# processor_breakout_conn.net
KiCad netlist of a schematic drawn in Altium Designer
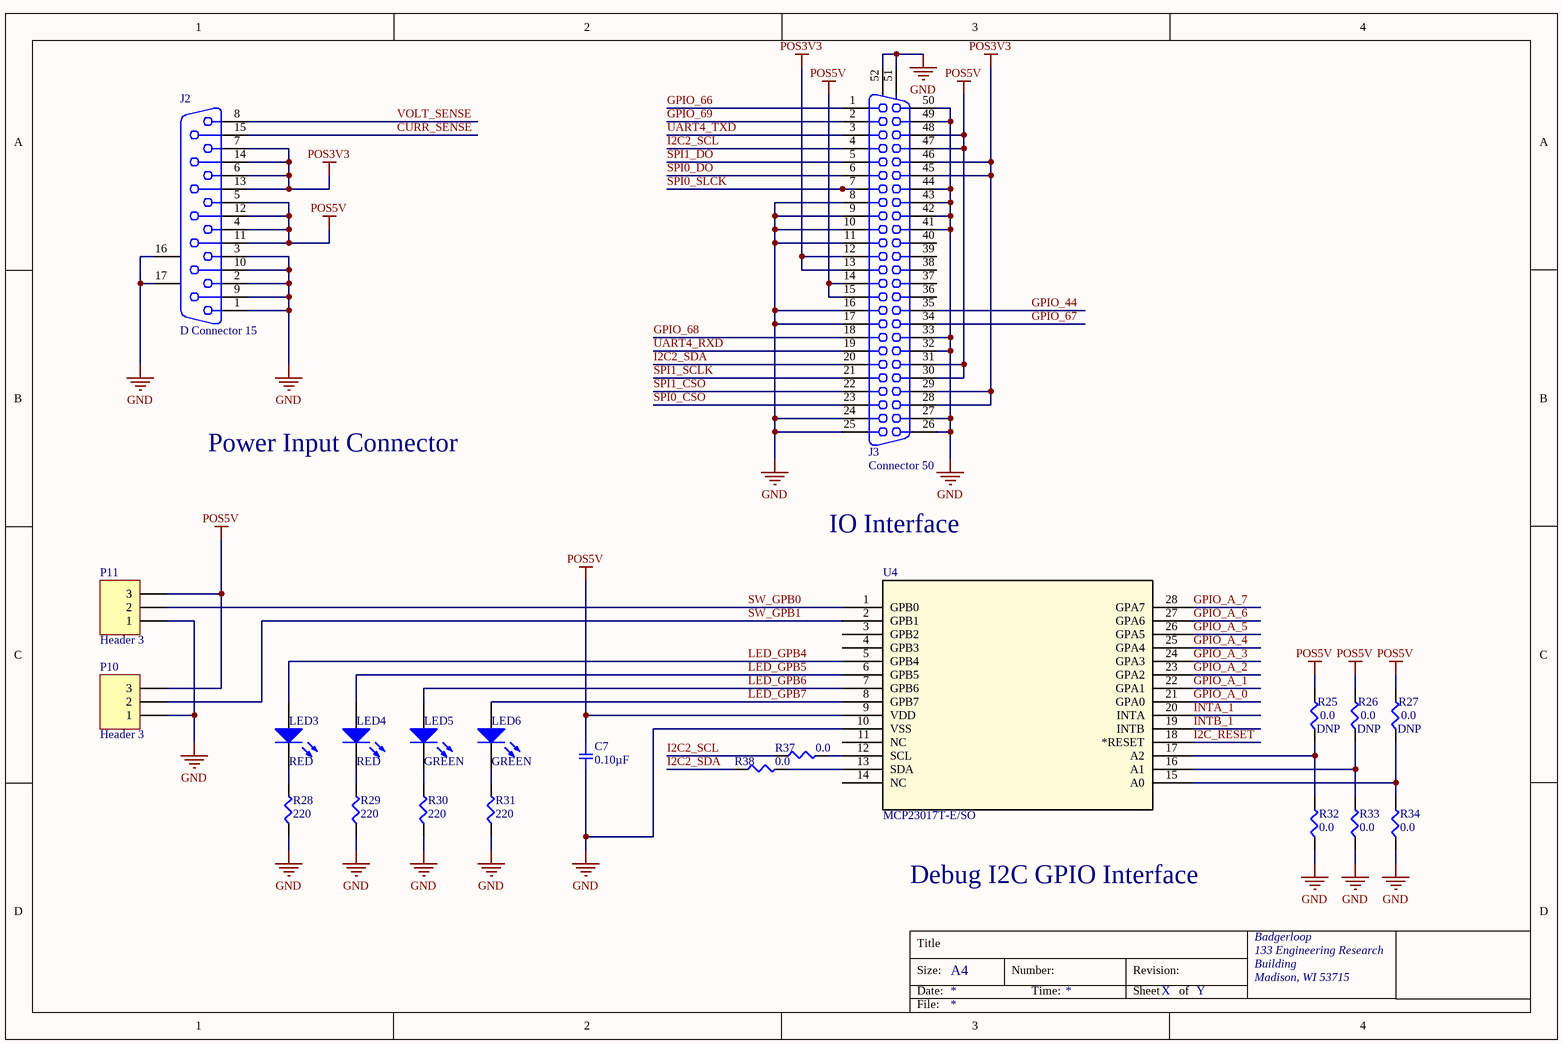
[diagram p0: processor_breakout_conn.SchDoc]

(export (version "E")
  (design (tool "Eeschema 10.0.6"))
  (components
    (comp (ref "C7")
      (value "0.10µF")
      (footprint "SMD-0603C")
      (description "CAP CER 0.1UF 100V X7R 0603")
      (fields
        (field (name "DIGI-KEY PART NUMBER") "490-13420-1-ND")
        (field (name "PART NUMBER") "GCJ188R72A104KA01D")
      )
      (libsource (lib "capacitor") (part "GCJ188R72A104KA01D"))
    )
    (comp (ref "J2")
      (value "D Connector 15")
      (footprint "DSUB1.385-2H15")
      (description "Receptacle Assembly, 15 Position, Right Angle")
      (fields (field (name "PUBLISHER") "Altium Limited"))
      (libsource (lib "connector") (part "D Connector 15"))
    )
    (comp (ref "J3")
      (value "Connector 50")
      (footprint "050DSUB1.27-H96")
      (description "Receptacle Header Assemby")
      (fields (field (name "PUBLISHER") "Altium Limited"))
      (libsource (lib "temp") (part "Connector 50"))
    )
    (comp (ref "LED3")
      (value "RED")
      (footprint "LED 0603 RED")
      (description "Red 631nm LED Indication - Discrete 2V 0603 (1608 Metric)")
      (fields (field (name "MANUFACTURER") "Lite-On Inc."))
      (libsource (lib "misc") (part "LED RED 0603"))
    )
    (comp (ref "LED4")
      (value "RED")
      (footprint "LED 0603 RED")
      (description "Red 631nm LED Indication - Discrete 2V 0603 (1608 Metric)")
      (fields (field (name "MANUFACTURER") "Lite-On Inc."))
      (libsource (lib "misc") (part "LED RED 0603"))
    )
    (comp (ref "LED5")
      (value "GREEN")
      (footprint "LED 0603 GREEN")
      (fields (field (name "MANUFACTURER") "Lite-On Inc."))
      (libsource (lib "misc") (part "LED GREEN 0603"))
    )
    (comp (ref "LED6")
      (value "GREEN")
      (footprint "LED 0603 GREEN")
      (fields (field (name "MANUFACTURER") "Lite-On Inc."))
      (libsource (lib "misc") (part "LED GREEN 0603"))
    )
    (comp (ref "P10")
      (value "Header 3")
      (footprint "Pin Header 1x3 TH Pitch 2.54mm")
      (description "Header, 3-Pin")
      (fields (field (name "PUBLISHER") "Altium Limited"))
      (libsource (lib "connector") (part "Header 3"))
    )
    (comp (ref "P11")
      (value "Header 3")
      (footprint "Pin Header 1x3 TH Pitch 2.54mm")
      (description "Header, 3-Pin")
      (fields (field (name "PUBLISHER") "Altium Limited"))
      (libsource (lib "connector") (part "Header 3"))
    )
    (comp (ref "R25")
      (value "0.0")
      (footprint "SMD-0402-RES")
      (description "RES SMD 0.0OHM JUMPER 1/10W 0402")
      (fields
        (field (name "PART NUMBER") "ERJ-2GE0R00X")
        (field (name "DIGI-KEY PART NUMBER") "P0.0JCT-ND")
        (field (name "DNP") "DNP")
      )
      (libsource (lib "resistor") (part "ERJ-2GE0R00X"))
    )
    (comp (ref "R26")
      (value "0.0")
      (footprint "SMD-0402-RES")
      (description "RES SMD 0.0OHM JUMPER 1/10W 0402")
      (fields
        (field (name "PART NUMBER") "ERJ-2GE0R00X")
        (field (name "DIGI-KEY PART NUMBER") "P0.0JCT-ND")
        (field (name "DNP") "DNP")
      )
      (libsource (lib "resistor") (part "ERJ-2GE0R00X"))
    )
    (comp (ref "R27")
      (value "0.0")
      (footprint "SMD-0402-RES")
      (description "RES SMD 0.0OHM JUMPER 1/10W 0402")
      (fields
        (field (name "PART NUMBER") "ERJ-2GE0R00X")
        (field (name "DIGI-KEY PART NUMBER") "P0.0JCT-ND")
        (field (name "DNP") "DNP")
      )
      (libsource (lib "resistor") (part "ERJ-2GE0R00X"))
    )
    (comp (ref "R28")
      (value "220")
      (footprint "SMD-0805-RES")
      (description "RES SMD 220 OHM 1% 1/8W 0805")
      (fields (field (name "PART NUMBER") "ERJ-6ENF2200V") (field (name "DIGI-KEY PART NUMBER") "P220CCT-ND"))
      (libsource (lib "resistor") (part "ERJ-6ENF2200V"))
    )
    (comp (ref "R29")
      (value "220")
      (footprint "SMD-0805-RES")
      (description "RES SMD 220 OHM 1% 1/8W 0805")
      (fields (field (name "PART NUMBER") "ERJ-6ENF2200V") (field (name "DIGI-KEY PART NUMBER") "P220CCT-ND"))
      (libsource (lib "resistor") (part "ERJ-6ENF2200V"))
    )
    (comp (ref "R30")
      (value "220")
      (footprint "SMD-0805-RES")
      (description "RES SMD 220 OHM 1% 1/8W 0805")
      (fields (field (name "PART NUMBER") "ERJ-6ENF2200V") (field (name "DIGI-KEY PART NUMBER") "P220CCT-ND"))
      (libsource (lib "resistor") (part "ERJ-6ENF2200V"))
    )
    (comp (ref "R31")
      (value "220")
      (footprint "SMD-0805-RES")
      (description "RES SMD 220 OHM 1% 1/8W 0805")
      (fields (field (name "PART NUMBER") "ERJ-6ENF2200V") (field (name "DIGI-KEY PART NUMBER") "P220CCT-ND"))
      (libsource (lib "resistor") (part "ERJ-6ENF2200V"))
    )
    (comp (ref "R32")
      (value "0.0")
      (footprint "SMD-0402-RES")
      (description "RES SMD 0.0OHM JUMPER 1/10W 0402")
      (fields (field (name "PART NUMBER") "ERJ-2GE0R00X") (field (name "DIGI-KEY PART NUMBER") "P0.0JCT-ND"))
      (libsource (lib "resistor") (part "ERJ-2GE0R00X"))
    )
    (comp (ref "R33")
      (value "0.0")
      (footprint "SMD-0402-RES")
      (description "RES SMD 0.0OHM JUMPER 1/10W 0402")
      (fields (field (name "PART NUMBER") "ERJ-2GE0R00X") (field (name "DIGI-KEY PART NUMBER") "P0.0JCT-ND"))
      (libsource (lib "resistor") (part "ERJ-2GE0R00X"))
    )
    (comp (ref "R34")
      (value "0.0")
      (footprint "SMD-0402-RES")
      (description "RES SMD 0.0OHM JUMPER 1/10W 0402")
      (fields (field (name "PART NUMBER") "ERJ-2GE0R00X") (field (name "DIGI-KEY PART NUMBER") "P0.0JCT-ND"))
      (libsource (lib "resistor") (part "ERJ-2GE0R00X"))
    )
    (comp (ref "R37")
      (value "0.0")
      (footprint "SMD-0402-RES")
      (description "RES SMD 0.0OHM JUMPER 1/10W 0402")
      (fields (field (name "PART NUMBER") "ERJ-2GE0R00X") (field (name "DIGI-KEY PART NUMBER") "P0.0JCT-ND"))
      (libsource (lib "resistor") (part "ERJ-2GE0R00X"))
    )
    (comp (ref "R38")
      (value "0.0")
      (footprint "SMD-0402-RES")
      (description "RES SMD 0.0OHM JUMPER 1/10W 0402")
      (fields (field (name "PART NUMBER") "ERJ-2GE0R00X") (field (name "DIGI-KEY PART NUMBER") "P0.0JCT-ND"))
      (libsource (lib "resistor") (part "ERJ-2GE0R00X"))
    )
    (comp (ref "U4")
      (value "MCP23017T-E/SO")
      (footprint "SOIC28-W_MC-M")
      (description "Imported")
      (libsource (lib "temp") (part "MCP23017T-E/SO"))
    )
  )
  (nets
    (net (code "1") (name "/CURR_SENSE") (class "Default")
      (node (ref "J2") (pin "15") (pinfunction "15_15") (pintype "passive"))
    )
    (net (code "2") (name "/GPIO_44") (class "Default")
      (node (ref "J3") (pin "35") (pinfunction "35_35") (pintype "passive"))
    )
    (net (code "3") (name "/GPIO_66") (class "Default")
      (node (ref "J3") (pin "1") (pinfunction "1_1") (pintype "passive"))
    )
    (net (code "4") (name "/GPIO_67") (class "Default")
      (node (ref "J3") (pin "34") (pinfunction "34_34") (pintype "passive"))
    )
    (net (code "5") (name "/GPIO_68") (class "Default")
      (node (ref "J3") (pin "18") (pinfunction "18_18") (pintype "passive"))
    )
    (net (code "6") (name "/GPIO_69") (class "Default")
      (node (ref "J3") (pin "2") (pinfunction "2_2") (pintype "passive"))
    )
    (net (code "7") (name "/GPIO_A_0") (class "Default")
      (node (ref "U4") (pin "21") (pinfunction "GPA0_21") (pintype "passive"))
    )
    (net (code "8") (name "/GPIO_A_1") (class "Default")
      (node (ref "U4") (pin "22") (pinfunction "GPA1_22") (pintype "passive"))
    )
    (net (code "9") (name "/GPIO_A_2") (class "Default")
      (node (ref "U4") (pin "23") (pinfunction "GPA2_23") (pintype "passive"))
    )
    (net (code "10") (name "/GPIO_A_3") (class "Default")
      (node (ref "U4") (pin "24") (pinfunction "GPA3_24") (pintype "passive"))
    )
    (net (code "11") (name "/GPIO_A_4") (class "Default")
      (node (ref "U4") (pin "25") (pinfunction "GPA4_25") (pintype "passive"))
    )
    (net (code "12") (name "/GPIO_A_5") (class "Default")
      (node (ref "U4") (pin "26") (pinfunction "GPA5_26") (pintype "passive"))
    )
    (net (code "13") (name "/GPIO_A_6") (class "Default")
      (node (ref "U4") (pin "27") (pinfunction "GPA6_27") (pintype "passive"))
    )
    (net (code "14") (name "/GPIO_A_7") (class "Default")
      (node (ref "U4") (pin "28") (pinfunction "GPA7_28") (pintype "passive"))
    )
    (net (code "15") (name "/I2C2_SCL") (class "Default")
      (node (ref "J3") (pin "4") (pinfunction "4_4") (pintype "passive"))
      (node (ref "R37") (pin "1") (pinfunction "1_1") (pintype "passive"))
    )
    (net (code "16") (name "/I2C2_SDA") (class "Default")
      (node (ref "J3") (pin "20") (pinfunction "20_20") (pintype "passive"))
      (node (ref "R38") (pin "1") (pinfunction "1_1") (pintype "passive"))
    )
    (net (code "17") (name "/I2C_RESET") (class "Default")
      (node (ref "U4") (pin "18") (pinfunction "*RESET_18") (pintype "passive"))
    )
    (net (code "18") (name "/INTA_1") (class "Default")
      (node (ref "U4") (pin "20") (pinfunction "INTA_20") (pintype "passive"))
    )
    (net (code "19") (name "/INTB_1") (class "Default")
      (node (ref "U4") (pin "19") (pinfunction "INTB_19") (pintype "passive"))
    )
    (net (code "20") (name "/LED_GPB4") (class "Default")
      (node (ref "LED3") (pin "1") (pinfunction "A_1") (pintype "passive"))
      (node (ref "U4") (pin "5") (pinfunction "GPB4_5") (pintype "passive"))
    )
    (net (code "21") (name "/LED_GPB5") (class "Default")
      (node (ref "LED4") (pin "1") (pinfunction "A_1") (pintype "passive"))
      (node (ref "U4") (pin "6") (pinfunction "GPB5_6") (pintype "passive"))
    )
    (net (code "22") (name "/LED_GPB6") (class "Default")
      (node (ref "LED5") (pin "1") (pinfunction "A_1") (pintype "passive"))
      (node (ref "U4") (pin "7") (pinfunction "GPB6_7") (pintype "passive"))
    )
    (net (code "23") (name "/LED_GPB7") (class "Default")
      (node (ref "LED6") (pin "1") (pinfunction "A_1") (pintype "passive"))
      (node (ref "U4") (pin "8") (pinfunction "GPB7_8") (pintype "passive"))
    )
    (net (code "24") (name "/SPI0_CSO") (class "Default")
      (node (ref "J3") (pin "23") (pinfunction "23_23") (pintype "passive"))
    )
    (net (code "25") (name "/SPI0_DO") (class "Default")
      (node (ref "J3") (pin "6") (pinfunction "6_6") (pintype "passive"))
    )
    (net (code "26") (name "/SPI0_SLCK") (class "Default")
      (node (ref "J3") (pin "7") (pinfunction "7_7") (pintype "passive"))
    )
    (net (code "27") (name "/SPI1_CSO") (class "Default")
      (node (ref "J3") (pin "22") (pinfunction "22_22") (pintype "passive"))
    )
    (net (code "28") (name "/SPI1_DO") (class "Default")
      (node (ref "J3") (pin "5") (pinfunction "5_5") (pintype "passive"))
    )
    (net (code "29") (name "/SPI1_SCLK") (class "Default")
      (node (ref "J3") (pin "21") (pinfunction "21_21") (pintype "passive"))
    )
    (net (code "30") (name "/SW_GPB0") (class "Default")
      (node (ref "P11") (pin "2") (pinfunction "2_2") (pintype "passive"))
      (node (ref "U4") (pin "1") (pinfunction "GPB0_1") (pintype "passive"))
    )
    (net (code "31") (name "/SW_GPB1") (class "Default")
      (node (ref "P10") (pin "2") (pinfunction "2_2") (pintype "passive"))
      (node (ref "U4") (pin "2") (pinfunction "GPB1_2") (pintype "passive"))
    )
    (net (code "32") (name "/UART4_RXD") (class "Default")
      (node (ref "J3") (pin "19") (pinfunction "19_19") (pintype "passive"))
    )
    (net (code "33") (name "/UART4_TXD") (class "Default")
      (node (ref "J3") (pin "3") (pinfunction "3_3") (pintype "passive"))
    )
    (net (code "34") (name "/VOLT_SENSE") (class "Default")
      (node (ref "J2") (pin "8") (pinfunction "8_8") (pintype "passive"))
    )
    (net (code "35") (name "GND") (class "Default")
      (node (ref "C7") (pin "2") (pinfunction "2_2") (pintype "passive"))
      (node (ref "J2") (pin "1") (pinfunction "1_1") (pintype "passive"))
      (node (ref "J2") (pin "10") (pinfunction "10_10") (pintype "passive"))
      (node (ref "J2") (pin "16") (pinfunction "MH1_16") (pintype "passive"))
      (node (ref "J2") (pin "17") (pinfunction "MH2_17") (pintype "passive"))
      (node (ref "J2") (pin "2") (pinfunction "2_2") (pintype "passive"))
      (node (ref "J2") (pin "3") (pinfunction "3_3") (pintype "passive"))
      (node (ref "J2") (pin "9") (pinfunction "9_9") (pintype "passive"))
      (node (ref "J3") (pin "10") (pinfunction "10_10") (pintype "passive"))
      (node (ref "J3") (pin "11") (pinfunction "11_11") (pintype "passive"))
      (node (ref "J3") (pin "16") (pinfunction "16_16") (pintype "passive"))
      (node (ref "J3") (pin "17") (pinfunction "17_17") (pintype "passive"))
      (node (ref "J3") (pin "24") (pinfunction "24_24") (pintype "passive"))
      (node (ref "J3") (pin "25") (pinfunction "25_25") (pintype "passive"))
      (node (ref "J3") (pin "26") (pinfunction "26_26") (pintype "passive"))
      (node (ref "J3") (pin "27") (pinfunction "27_27") (pintype "passive"))
      (node (ref "J3") (pin "32") (pinfunction "32_32") (pintype "passive"))
      (node (ref "J3") (pin "33") (pinfunction "33_33") (pintype "passive"))
      (node (ref "J3") (pin "41") (pinfunction "41_41") (pintype "passive"))
      (node (ref "J3") (pin "42") (pinfunction "42_42") (pintype "passive"))
      (node (ref "J3") (pin "43") (pinfunction "43_43") (pintype "passive"))
      (node (ref "J3") (pin "44") (pinfunction "44_44") (pintype "passive"))
      (node (ref "J3") (pin "49") (pinfunction "49_49") (pintype "passive"))
      (node (ref "J3") (pin "50") (pinfunction "50_50") (pintype "passive"))
      (node (ref "J3") (pin "51") (pinfunction "51_51") (pintype "passive"))
      (node (ref "J3") (pin "52") (pinfunction "52_52") (pintype "passive"))
      (node (ref "J3") (pin "8") (pinfunction "8_8") (pintype "passive"))
      (node (ref "J3") (pin "9") (pinfunction "9_9") (pintype "passive"))
      (node (ref "P10") (pin "1") (pinfunction "1_1") (pintype "passive"))
      (node (ref "P11") (pin "1") (pinfunction "1_1") (pintype "passive"))
      (node (ref "R28") (pin "1") (pinfunction "1_1") (pintype "passive"))
      (node (ref "R29") (pin "1") (pinfunction "1_1") (pintype "passive"))
      (node (ref "R30") (pin "1") (pinfunction "1_1") (pintype "passive"))
      (node (ref "R31") (pin "1") (pinfunction "1_1") (pintype "passive"))
      (node (ref "R32") (pin "1") (pinfunction "1_1") (pintype "passive"))
      (node (ref "R33") (pin "1") (pinfunction "1_1") (pintype "passive"))
      (node (ref "R34") (pin "1") (pinfunction "1_1") (pintype "passive"))
      (node (ref "U4") (pin "10") (pinfunction "VSS_10") (pintype "passive"))
    )
    (net (code "36") (name "Net-(LED3-K)") (class "Default")
      (node (ref "LED3") (pin "2") (pinfunction "K_2") (pintype "passive"))
      (node (ref "R28") (pin "2") (pinfunction "2_2") (pintype "passive"))
    )
    (net (code "37") (name "Net-(LED4-K)") (class "Default")
      (node (ref "LED4") (pin "2") (pinfunction "K_2") (pintype "passive"))
      (node (ref "R29") (pin "2") (pinfunction "2_2") (pintype "passive"))
    )
    (net (code "38") (name "Net-(LED5-K)") (class "Default")
      (node (ref "LED5") (pin "2") (pinfunction "K_2") (pintype "passive"))
      (node (ref "R30") (pin "2") (pinfunction "2_2") (pintype "passive"))
    )
    (net (code "39") (name "Net-(LED6-K)") (class "Default")
      (node (ref "LED6") (pin "2") (pinfunction "K_2") (pintype "passive"))
      (node (ref "R31") (pin "2") (pinfunction "2_2") (pintype "passive"))
    )
    (net (code "40") (name "Net-(U4-A0)") (class "Default")
      (node (ref "R27") (pin "1") (pinfunction "1_1") (pintype "passive"))
      (node (ref "R34") (pin "2") (pinfunction "2_2") (pintype "passive"))
      (node (ref "U4") (pin "15") (pinfunction "A0_15") (pintype "passive"))
    )
    (net (code "41") (name "Net-(U4-A1)") (class "Default")
      (node (ref "R26") (pin "1") (pinfunction "1_1") (pintype "passive"))
      (node (ref "R33") (pin "2") (pinfunction "2_2") (pintype "passive"))
      (node (ref "U4") (pin "16") (pinfunction "A1_16") (pintype "passive"))
    )
    (net (code "42") (name "Net-(U4-A2)") (class "Default")
      (node (ref "R25") (pin "1") (pinfunction "1_1") (pintype "passive"))
      (node (ref "R32") (pin "2") (pinfunction "2_2") (pintype "passive"))
      (node (ref "U4") (pin "17") (pinfunction "A2_17") (pintype "passive"))
    )
    (net (code "43") (name "Net-(U4-SCL)") (class "Default")
      (node (ref "R37") (pin "2") (pinfunction "2_2") (pintype "passive"))
      (node (ref "U4") (pin "12") (pinfunction "SCL_12") (pintype "passive"))
    )
    (net (code "44") (name "Net-(U4-SDA)") (class "Default")
      (node (ref "R38") (pin "2") (pinfunction "2_2") (pintype "passive"))
      (node (ref "U4") (pin "13") (pinfunction "SDA_13") (pintype "passive"))
    )
    (net (code "45") (name "POS3V3") (class "Default")
      (node (ref "J2") (pin "13") (pinfunction "13_13") (pintype "passive"))
      (node (ref "J2") (pin "14") (pinfunction "14_14") (pintype "passive"))
      (node (ref "J2") (pin "6") (pinfunction "6_6") (pintype "passive"))
      (node (ref "J2") (pin "7") (pinfunction "7_7") (pintype "passive"))
      (node (ref "J3") (pin "12") (pinfunction "12_12") (pintype "passive"))
      (node (ref "J3") (pin "13") (pinfunction "13_13") (pintype "passive"))
      (node (ref "J3") (pin "28") (pinfunction "28_28") (pintype "passive"))
      (node (ref "J3") (pin "29") (pinfunction "29_29") (pintype "passive"))
      (node (ref "J3") (pin "45") (pinfunction "45_45") (pintype "passive"))
      (node (ref "J3") (pin "46") (pinfunction "46_46") (pintype "passive"))
    )
    (net (code "46") (name "POS5V") (class "Default")
      (node (ref "C7") (pin "1") (pinfunction "1_1") (pintype "passive"))
      (node (ref "J2") (pin "11") (pinfunction "11_11") (pintype "passive"))
      (node (ref "J2") (pin "12") (pinfunction "12_12") (pintype "passive"))
      (node (ref "J2") (pin "4") (pinfunction "4_4") (pintype "passive"))
      (node (ref "J2") (pin "5") (pinfunction "5_5") (pintype "passive"))
      (node (ref "J3") (pin "14") (pinfunction "14_14") (pintype "passive"))
      (node (ref "J3") (pin "15") (pinfunction "15_15") (pintype "passive"))
      (node (ref "J3") (pin "30") (pinfunction "30_30") (pintype "passive"))
      (node (ref "J3") (pin "31") (pinfunction "31_31") (pintype "passive"))
      (node (ref "J3") (pin "47") (pinfunction "47_47") (pintype "passive"))
      (node (ref "J3") (pin "48") (pinfunction "48_48") (pintype "passive"))
      (node (ref "P10") (pin "3") (pinfunction "3_3") (pintype "passive"))
      (node (ref "P11") (pin "3") (pinfunction "3_3") (pintype "passive"))
      (node (ref "R25") (pin "2") (pinfunction "2_2") (pintype "passive"))
      (node (ref "R26") (pin "2") (pinfunction "2_2") (pintype "passive"))
      (node (ref "R27") (pin "2") (pinfunction "2_2") (pintype "passive"))
      (node (ref "U4") (pin "9") (pinfunction "VDD_9") (pintype "passive"))
    )
    (net (code "47") (name "unconnected-(J3-Pad36)") (class "Default")
      (node (ref "J3") (pin "36") (pinfunction "36_36") (pintype "passive"))
    )
    (net (code "48") (name "unconnected-(J3-Pad37)") (class "Default")
      (node (ref "J3") (pin "37") (pinfunction "37_37") (pintype "passive"))
    )
    (net (code "49") (name "unconnected-(J3-Pad38)") (class "Default")
      (node (ref "J3") (pin "38") (pinfunction "38_38") (pintype "passive"))
    )
    (net (code "50") (name "unconnected-(J3-Pad39)") (class "Default")
      (node (ref "J3") (pin "39") (pinfunction "39_39") (pintype "passive"))
    )
    (net (code "51") (name "unconnected-(J3-Pad40)") (class "Default")
      (node (ref "J3") (pin "40") (pinfunction "40_40") (pintype "passive"))
    )
    (net (code "52") (name "unconnected-(U4-GPB2-Pad3)") (class "Default")
      (node (ref "U4") (pin "3") (pinfunction "GPB2_3") (pintype "passive"))
    )
    (net (code "53") (name "unconnected-(U4-GPB3-Pad4)") (class "Default")
      (node (ref "U4") (pin "4") (pinfunction "GPB3_4") (pintype "passive"))
    )
    (net (code "54") (name "unconnected-(U4-NC-Pad11)") (class "Default")
      (node (ref "U4") (pin "11") (pinfunction "NC_11") (pintype "passive"))
    )
    (net (code "55") (name "unconnected-(U4-NC-Pad14)") (class "Default")
      (node (ref "U4") (pin "14") (pinfunction "NC_14") (pintype "passive"))
    )
  )
)
